# T-11_Version_1_00.net
KiCad netlist of a schematic drawn in EAGLE
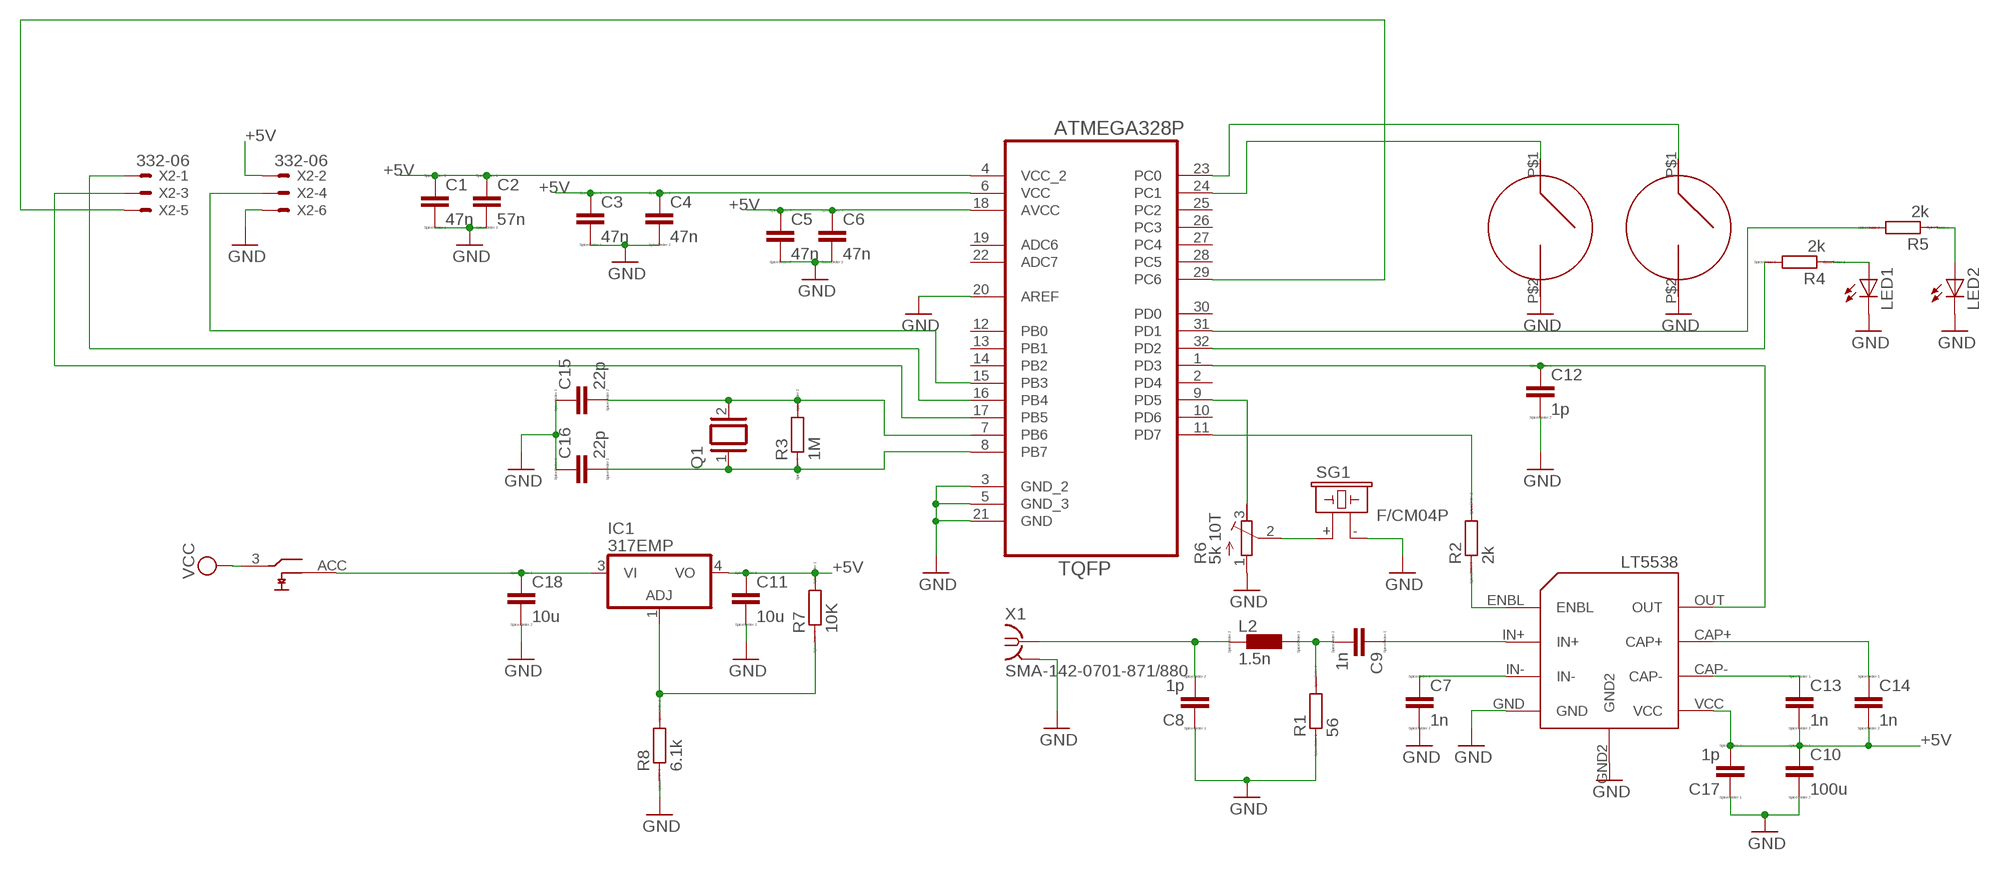
[diagram p0: schematic, sheet 1]

(export (version "E")
  (design (tool "Eeschema 10.0.6"))
  (components
    (comp (ref "C1")
      (value "47n")
      (footprint "eagle-import:C4532")
      (libsource (lib "eagle-import") (part "CC4532"))
    )
    (comp (ref "C2")
      (value "57n")
      (footprint "eagle-import:C4532")
      (libsource (lib "eagle-import") (part "CC4532"))
    )
    (comp (ref "C3")
      (value "47n")
      (footprint "eagle-import:C4532")
      (libsource (lib "eagle-import") (part "CC4532"))
    )
    (comp (ref "C4")
      (value "47n")
      (footprint "eagle-import:C4532")
      (libsource (lib "eagle-import") (part "CC4532"))
    )
    (comp (ref "C5")
      (value "47n")
      (footprint "eagle-import:C4532")
      (libsource (lib "eagle-import") (part "CC4532"))
    )
    (comp (ref "C6")
      (value "47n")
      (footprint "eagle-import:C4532")
      (libsource (lib "eagle-import") (part "CC4532"))
    )
    (comp (ref "C7")
      (value "1n")
      (footprint "eagle-import:C4532")
      (libsource (lib "eagle-import") (part "CC4532"))
    )
    (comp (ref "C8")
      (value "1p")
      (footprint "eagle-import:C4532")
      (libsource (lib "eagle-import") (part "CC4532"))
    )
    (comp (ref "C9")
      (value "1n")
      (footprint "eagle-import:C4532")
      (libsource (lib "eagle-import") (part "CC4532"))
    )
    (comp (ref "C10")
      (value "100u")
      (footprint "eagle-import:C4532")
      (libsource (lib "eagle-import") (part "CC4532"))
    )
    (comp (ref "C11")
      (value "10u")
      (footprint "eagle-import:C4532")
      (libsource (lib "eagle-import") (part "CC4532"))
    )
    (comp (ref "C12")
      (value "1p")
      (footprint "eagle-import:C0805")
      (fields (field (name "SPICEMODEL") "1p"))
      (libsource (lib "eagle-import") (part "C"))
    )
    (comp (ref "C13")
      (value "1n")
      (footprint "eagle-import:C4532")
      (libsource (lib "eagle-import") (part "CC4532"))
    )
    (comp (ref "C14")
      (value "1n")
      (footprint "eagle-import:C4532")
      (libsource (lib "eagle-import") (part "CC4532"))
    )
    (comp (ref "C15")
      (value "22p")
      (footprint "eagle-import:C4532")
      (libsource (lib "eagle-import") (part "CC4532"))
    )
    (comp (ref "C16")
      (value "22p")
      (footprint "eagle-import:C4532")
      (libsource (lib "eagle-import") (part "CC4532"))
    )
    (comp (ref "C17")
      (value "1p")
      (footprint "eagle-import:C4532")
      (libsource (lib "eagle-import") (part "CC4532"))
    )
    (comp (ref "C18")
      (value "10u")
      (footprint "eagle-import:C4532")
      (libsource (lib "eagle-import") (part "CC4532"))
    )
    (comp (ref "IC1")
      (value "317EMP")
      (footprint "eagle-import:SOT223")
      (libsource (lib "eagle-import") (part "317EMP"))
    )
    (comp (ref "L2")
      (value "1.5n")
      (footprint "eagle-import:L4532P")
      (libsource (lib "eagle-import") (part "LL4532P"))
    )
    (comp (ref "LED1")
      (value "LED3MM")
      (footprint "eagle-import:LED3MM")
      (libsource (lib "eagle-import") (part "LED3MM"))
    )
    (comp (ref "LED2")
      (value "LED3MM")
      (footprint "eagle-import:LED3MM")
      (libsource (lib "eagle-import") (part "LED3MM"))
    )
    (comp (ref "Q1")
      (value "XTAL")
      (footprint "eagle-import:Q")
      (libsource (lib "eagle-import") (part "XTAL"))
    )
    (comp (ref "R1")
      (value "56")
      (footprint "eagle-import:R3225")
      (libsource (lib "eagle-import") (part "RR3225"))
    )
    (comp (ref "R2")
      (value "2k")
      (footprint "eagle-import:R3225")
      (libsource (lib "eagle-import") (part "RR3225"))
    )
    (comp (ref "R3")
      (value "1M")
      (footprint "eagle-import:R3225")
      (libsource (lib "eagle-import") (part "RR3225"))
    )
    (comp (ref "R4")
      (value "2k")
      (footprint "eagle-import:R3225")
      (libsource (lib "eagle-import") (part "RR3225"))
    )
    (comp (ref "R5")
      (value "2k")
      (footprint "eagle-import:R3225")
      (libsource (lib "eagle-import") (part "RR3225"))
    )
    (comp (ref "R6")
      (value "5k 10T")
      (footprint "eagle-import:RTRIMTS63Y")
      (libsource (lib "eagle-import") (part "R-TRIMMTS63Y"))
    )
    (comp (ref "R7")
      (value "10K")
      (footprint "eagle-import:R3225")
      (libsource (lib "eagle-import") (part "RR3225"))
    )
    (comp (ref "R8")
      (value "6.1k")
      (footprint "eagle-import:R3225")
      (libsource (lib "eagle-import") (part "RR3225"))
    )
    (comp (ref "SG1")
      (value "F/CM04P")
      (footprint "eagle-import:F_CM04P")
      (libsource (lib "eagle-import") (part "F/CM04P"))
    )
    (comp (ref "U$1")
      (value "LT5538")
      (footprint "eagle-import:LT5538")
      (libsource (lib "eagle-import") (part "LT5538"))
    )
    (comp (ref "U$2")
      (value "SW-1801X")
      (footprint "eagle-import:SW-1801X")
      (libsource (lib "eagle-import") (part "SW-1801X"))
    )
    (comp (ref "U$3")
      (value "SW-1801X")
      (footprint "eagle-import:SW-1801X")
      (libsource (lib "eagle-import") (part "SW-1801X"))
    )
    (comp (ref "U$4")
      (value "275-0601")
      (footprint "eagle-import:M9040P")
      (libsource (lib "eagle-import") (part "275-0601"))
    )
    (comp (ref "U1")
      (value "ATMEGA328P-AU")
      (footprint "eagle-import:QFP80P900X900X120-32N")
      (libsource (lib "eagle-import") (part "ATMEGA328P-AU"))
    )
    (comp (ref "X1")
      (value "SMA-142-0701-871/880")
      (footprint "eagle-import:SMA-142-0701-871")
      (fields (field (name "MF") "JOHNSON COMPONENTS") (field (name "MPN") "142-0701-871"))
      (libsource (lib "eagle-import") (part "SMA-142-0701-871/880"))
    )
    (comp (ref "X2")
      (value "332-06")
      (footprint "eagle-import:332-06")
      (libsource (lib "eagle-import") (part "332-06"))
    )
  )
  (nets
    (net (code "1") (name "/+5V") (class "Default")
      (node (ref "C1") (pin "1") (pinfunction "1_1") (pintype "passive"))
      (node (ref "C10") (pin "1") (pinfunction "1_1") (pintype "passive"))
      (node (ref "C11") (pin "1") (pinfunction "1_1") (pintype "passive"))
      (node (ref "C13") (pin "2") (pinfunction "2_2") (pintype "passive"))
      (node (ref "C14") (pin "2") (pinfunction "2_2") (pintype "passive"))
      (node (ref "C17") (pin "2") (pinfunction "2_2") (pintype "passive"))
      (node (ref "C2") (pin "1") (pinfunction "1_1") (pintype "passive"))
      (node (ref "C3") (pin "1") (pinfunction "1_1") (pintype "passive"))
      (node (ref "C4") (pin "1") (pinfunction "1_1") (pintype "passive"))
      (node (ref "C5") (pin "1") (pinfunction "1_1") (pintype "passive"))
      (node (ref "C6") (pin "1") (pinfunction "1_1") (pintype "passive"))
      (node (ref "IC1") (pin "4") (pinfunction "VO_4") (pintype "passive"))
      (node (ref "R7") (pin "2") (pinfunction "2_2") (pintype "passive"))
      (node (ref "U$1") (pin "VCC") (pinfunction "VCC_VCC") (pintype "power_in"))
      (node (ref "U1") (pin "18") (pinfunction "AVCC_18") (pintype "power_in"))
      (node (ref "U1") (pin "4") (pinfunction "VCC_2_4") (pintype "power_in"))
      (node (ref "U1") (pin "6") (pinfunction "VCC_6") (pintype "power_in"))
      (node (ref "X2") (pin "2") (pinfunction "S_2") (pintype "passive"))
    )
    (net (code "2") (name "/P$1") (class "Default")
      (node (ref "U$4") (pin "3") (pinfunction "P$1_3") (pintype "power_in"))
    )
    (net (code "3") (name "GND") (class "Default")
      (node (ref "C1") (pin "2") (pinfunction "2_2") (pintype "passive"))
      (node (ref "C10") (pin "2") (pinfunction "2_2") (pintype "passive"))
      (node (ref "C11") (pin "2") (pinfunction "2_2") (pintype "passive"))
      (node (ref "C12") (pin "2") (pinfunction "2_2") (pintype "passive"))
      (node (ref "C15") (pin "1") (pinfunction "1_1") (pintype "passive"))
      (node (ref "C16") (pin "1") (pinfunction "1_1") (pintype "passive"))
      (node (ref "C17") (pin "1") (pinfunction "1_1") (pintype "passive"))
      (node (ref "C18") (pin "2") (pinfunction "2_2") (pintype "passive"))
      (node (ref "C2") (pin "2") (pinfunction "2_2") (pintype "passive"))
      (node (ref "C3") (pin "2") (pinfunction "2_2") (pintype "passive"))
      (node (ref "C4") (pin "2") (pinfunction "2_2") (pintype "passive"))
      (node (ref "C5") (pin "2") (pinfunction "2_2") (pintype "passive"))
      (node (ref "C6") (pin "2") (pinfunction "2_2") (pintype "passive"))
      (node (ref "C7") (pin "2") (pinfunction "2_2") (pintype "passive"))
      (node (ref "C8") (pin "1") (pinfunction "1_1") (pintype "passive"))
      (node (ref "LED1") (pin "K") (pinfunction "C_K") (pintype "passive"))
      (node (ref "LED2") (pin "K") (pinfunction "C_K") (pintype "passive"))
      (node (ref "R1") (pin "1") (pinfunction "1_1") (pintype "passive"))
      (node (ref "R6") (pin "1") (pinfunction "A_1") (pintype "passive"))
      (node (ref "R8") (pin "1") (pinfunction "1_1") (pintype "passive"))
      (node (ref "SG1") (pin "-") (pinfunction "2_-") (pintype "passive"))
      (node (ref "U$1") (pin "GND") (pinfunction "GND_GND") (pintype "power_in"))
      (node (ref "U$1") (pin "GND2") (pinfunction "GND2_GND2") (pintype "bidirectional"))
      (node (ref "U$2") (pin "P$2") (pinfunction "P$2_P$2") (pintype "bidirectional"))
      (node (ref "U$3") (pin "P$2") (pinfunction "P$2_P$2") (pintype "bidirectional"))
      (node (ref "U1") (pin "20") (pinfunction "AREF_20") (pintype "input"))
      (node (ref "U1") (pin "21") (pinfunction "GND_21") (pintype "passive"))
      (node (ref "U1") (pin "3") (pinfunction "GND_2_3") (pintype "passive"))
      (node (ref "U1") (pin "5") (pinfunction "GND_3_5") (pintype "passive"))
      (node (ref "X1") (pin "2@1") (pinfunction "2_2@1") (pintype "passive"))
      (node (ref "X1") (pin "2@2") (pinfunction "2_2@2") (pintype "passive"))
      (node (ref "X1") (pin "2@3") (pinfunction "2_2@3") (pintype "passive"))
      (node (ref "X1") (pin "2@4") (pinfunction "2_2@4") (pintype "passive"))
      (node (ref "X2") (pin "6") (pinfunction "S_6") (pintype "passive"))
    )
    (net (code "4") (name "Net-(C7-Pad1)") (class "Default")
      (node (ref "C7") (pin "1") (pinfunction "1_1") (pintype "passive"))
      (node (ref "U$1") (pin "IN-") (pinfunction "IN-_IN-") (pintype "bidirectional"))
    )
    (net (code "5") (name "Net-(C8-Pad2)") (class "Default")
      (node (ref "C8") (pin "2") (pinfunction "2_2") (pintype "passive"))
      (node (ref "L2") (pin "2") (pinfunction "2_2") (pintype "passive"))
      (node (ref "X1") (pin "1") (pinfunction "1_1") (pintype "passive"))
    )
    (net (code "6") (name "Net-(C9-Pad1)") (class "Default")
      (node (ref "C9") (pin "1") (pinfunction "1_1") (pintype "passive"))
      (node (ref "U$1") (pin "IN+") (pinfunction "IN+_IN+") (pintype "bidirectional"))
    )
    (net (code "7") (name "Net-(C9-Pad2)") (class "Default")
      (node (ref "C9") (pin "2") (pinfunction "2_2") (pintype "passive"))
      (node (ref "L2") (pin "1") (pinfunction "1_1") (pintype "passive"))
      (node (ref "R1") (pin "2") (pinfunction "2_2") (pintype "passive"))
    )
    (net (code "8") (name "Net-(C13-Pad1)") (class "Default")
      (node (ref "C13") (pin "1") (pinfunction "1_1") (pintype "passive"))
      (node (ref "U$1") (pin "CAP-") (pinfunction "CAP-_CAP-") (pintype "bidirectional"))
    )
    (net (code "9") (name "Net-(C14-Pad1)") (class "Default")
      (node (ref "C14") (pin "1") (pinfunction "1_1") (pintype "passive"))
      (node (ref "U$1") (pin "CAP+") (pinfunction "CAP+_CAP+") (pintype "bidirectional"))
    )
    (net (code "10") (name "Net-(IC1-ADJ)") (class "Default")
      (node (ref "IC1") (pin "1") (pinfunction "ADJ_1") (pintype "input"))
      (node (ref "R7") (pin "1") (pinfunction "1_1") (pintype "passive"))
      (node (ref "R8") (pin "2") (pinfunction "2_2") (pintype "passive"))
    )
    (net (code "11") (name "Net-(IC1-VI)") (class "Default")
      (node (ref "C18") (pin "1") (pinfunction "1_1") (pintype "passive"))
      (node (ref "IC1") (pin "3") (pinfunction "VI_3") (pintype "input"))
    )
    (net (code "12") (name "Net-(LED1-PadA)") (class "Default")
      (node (ref "LED1") (pin "A") (pinfunction "A_A") (pintype "passive"))
      (node (ref "R4") (pin "1") (pinfunction "1_1") (pintype "passive"))
    )
    (net (code "13") (name "Net-(LED2-PadA)") (class "Default")
      (node (ref "LED2") (pin "A") (pinfunction "A_A") (pintype "passive"))
      (node (ref "R5") (pin "1") (pinfunction "1_1") (pintype "passive"))
    )
    (net (code "14") (name "Net-(R2-Pad1)") (class "Default")
      (node (ref "R2") (pin "1") (pinfunction "1_1") (pintype "passive"))
      (node (ref "U$1") (pin "ENBL") (pinfunction "ENBL_ENBL") (pintype "bidirectional"))
    )
    (net (code "15") (name "Net-(R6-E)") (class "Default")
      (node (ref "R6") (pin "3") (pinfunction "E_3") (pintype "passive"))
      (node (ref "U1") (pin "9") (pinfunction "PD5_9") (pintype "bidirectional"))
    )
    (net (code "16") (name "Net-(R6-S)") (class "Default")
      (node (ref "R6") (pin "2") (pinfunction "S_2") (pintype "passive"))
      (node (ref "SG1") (pin "+") (pinfunction "1_+") (pintype "passive"))
    )
    (net (code "17") (name "Net-(U1-PB3)") (class "Default")
      (node (ref "U1") (pin "15") (pinfunction "PB3_15") (pintype "bidirectional"))
      (node (ref "X2") (pin "4") (pinfunction "S_4") (pintype "passive"))
    )
    (net (code "18") (name "Net-(U1-PB4)") (class "Default")
      (node (ref "U1") (pin "16") (pinfunction "PB4_16") (pintype "bidirectional"))
      (node (ref "X2") (pin "1") (pinfunction "S_1") (pintype "passive"))
    )
    (net (code "19") (name "Net-(U1-PB5)") (class "Default")
      (node (ref "U1") (pin "17") (pinfunction "PB5_17") (pintype "bidirectional"))
      (node (ref "X2") (pin "3") (pinfunction "S_3") (pintype "passive"))
    )
    (net (code "20") (name "Net-(U1-PB6)") (class "Default")
      (node (ref "C15") (pin "2") (pinfunction "2_2") (pintype "passive"))
      (node (ref "Q1") (pin "2") (pinfunction "2_2") (pintype "passive"))
      (node (ref "R3") (pin "2") (pinfunction "2_2") (pintype "passive"))
      (node (ref "U1") (pin "7") (pinfunction "PB6_7") (pintype "bidirectional"))
    )
    (net (code "21") (name "Net-(U1-PB7)") (class "Default")
      (node (ref "C16") (pin "2") (pinfunction "2_2") (pintype "passive"))
      (node (ref "Q1") (pin "1") (pinfunction "1_1") (pintype "passive"))
      (node (ref "R3") (pin "1") (pinfunction "1_1") (pintype "passive"))
      (node (ref "U1") (pin "8") (pinfunction "PB7_8") (pintype "bidirectional"))
    )
    (net (code "22") (name "Net-(U1-PC0)") (class "Default")
      (node (ref "U$2") (pin "P$1") (pinfunction "P$1_P$1") (pintype "bidirectional"))
      (node (ref "U1") (pin "23") (pinfunction "PC0_23") (pintype "bidirectional"))
    )
    (net (code "23") (name "Net-(U1-PC1)") (class "Default")
      (node (ref "U$3") (pin "P$1") (pinfunction "P$1_P$1") (pintype "bidirectional"))
      (node (ref "U1") (pin "24") (pinfunction "PC1_24") (pintype "bidirectional"))
    )
    (net (code "24") (name "Net-(U1-PC6)") (class "Default")
      (node (ref "U1") (pin "29") (pinfunction "PC6_29") (pintype "bidirectional"))
      (node (ref "X2") (pin "5") (pinfunction "S_5") (pintype "passive"))
    )
    (net (code "25") (name "Net-(U1-PD1)") (class "Default")
      (node (ref "R5") (pin "2") (pinfunction "2_2") (pintype "passive"))
      (node (ref "U1") (pin "31") (pinfunction "PD1_31") (pintype "bidirectional"))
    )
    (net (code "26") (name "Net-(U1-PD2)") (class "Default")
      (node (ref "R4") (pin "2") (pinfunction "2_2") (pintype "passive"))
      (node (ref "U1") (pin "32") (pinfunction "PD2_32") (pintype "bidirectional"))
    )
    (net (code "27") (name "Net-(U1-PD3)") (class "Default")
      (node (ref "C12") (pin "1") (pinfunction "1_1") (pintype "passive"))
      (node (ref "U$1") (pin "OUT") (pinfunction "OUT_OUT") (pintype "output"))
      (node (ref "U1") (pin "1") (pinfunction "PD3_1") (pintype "bidirectional"))
    )
    (net (code "28") (name "Net-(U1-PD7)") (class "Default")
      (node (ref "R2") (pin "2") (pinfunction "2_2") (pintype "passive"))
      (node (ref "U1") (pin "11") (pinfunction "PD7_11") (pintype "bidirectional"))
    )
    (net (code "30") (name "unconnected-(U$4-P$2-PadACC)") (class "Default")
      (node (ref "U$4") (pin "ACC") (pinfunction "P$2_ACC") (pintype "output"))
    )
    (net (code "31") (name "unconnected-(U$4-PadGND)") (class "Default")
      (node (ref "U$4") (pin "GND") (pinfunction "GND_GND") (pintype "output"))
    )
    (net (code "32") (name "unconnected-(U1-ADC6-Pad19)") (class "Default")
      (node (ref "U1") (pin "19") (pinfunction "ADC6_19") (pintype "input"))
    )
    (net (code "33") (name "unconnected-(U1-ADC7-Pad22)") (class "Default")
      (node (ref "U1") (pin "22") (pinfunction "ADC7_22") (pintype "input"))
    )
    (net (code "34") (name "unconnected-(U1-PB0-Pad12)") (class "Default")
      (node (ref "U1") (pin "12") (pinfunction "PB0_12") (pintype "bidirectional"))
    )
    (net (code "35") (name "unconnected-(U1-PB1-Pad13)") (class "Default")
      (node (ref "U1") (pin "13") (pinfunction "PB1_13") (pintype "bidirectional"))
    )
    (net (code "36") (name "unconnected-(U1-PB2-Pad14)") (class "Default")
      (node (ref "U1") (pin "14") (pinfunction "PB2_14") (pintype "bidirectional"))
    )
    (net (code "37") (name "unconnected-(U1-PC2-Pad25)") (class "Default")
      (node (ref "U1") (pin "25") (pinfunction "PC2_25") (pintype "bidirectional"))
    )
    (net (code "38") (name "unconnected-(U1-PC3-Pad26)") (class "Default")
      (node (ref "U1") (pin "26") (pinfunction "PC3_26") (pintype "bidirectional"))
    )
    (net (code "39") (name "unconnected-(U1-PC4-Pad27)") (class "Default")
      (node (ref "U1") (pin "27") (pinfunction "PC4_27") (pintype "bidirectional"))
    )
    (net (code "40") (name "unconnected-(U1-PC5-Pad28)") (class "Default")
      (node (ref "U1") (pin "28") (pinfunction "PC5_28") (pintype "bidirectional"))
    )
    (net (code "41") (name "unconnected-(U1-PD0-Pad30)") (class "Default")
      (node (ref "U1") (pin "30") (pinfunction "PD0_30") (pintype "bidirectional"))
    )
    (net (code "42") (name "unconnected-(U1-PD4-Pad2)") (class "Default")
      (node (ref "U1") (pin "2") (pinfunction "PD4_2") (pintype "bidirectional"))
    )
    (net (code "43") (name "unconnected-(U1-PD6-Pad10)") (class "Default")
      (node (ref "U1") (pin "10") (pinfunction "PD6_10") (pintype "bidirectional"))
    )
  )
)
